# Relay_y_salida_anal_gica.net
KiCad netlist of a schematic drawn in Altium Designer
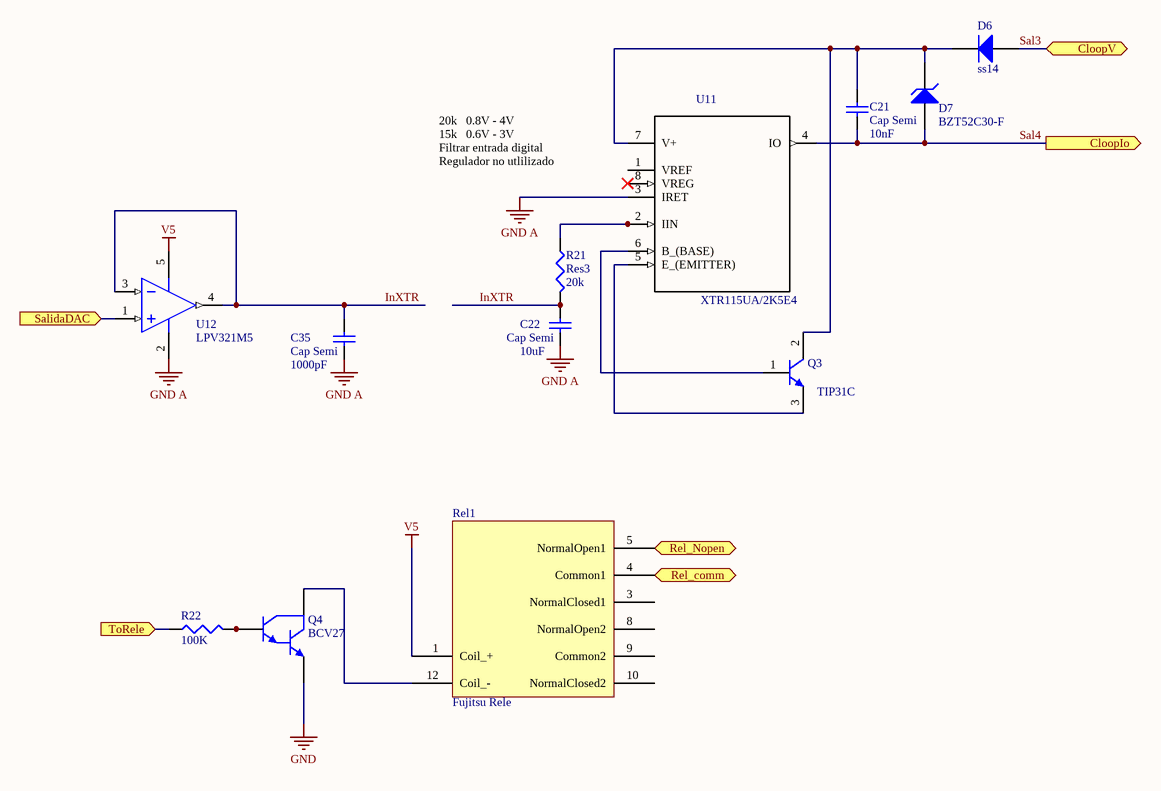
[diagram p0: Relay y salida analógica.SchDoc]

(export (version "E")
  (design (tool "Eeschema 10.0.6"))
  (components
    (comp (ref "C21")
      (value "Cap Semi")
      (footprint "Custom0805")
      (description "Capacitor (Semiconductor SIM Model)")
      (fields (field (name "ALTIUM_VALUE") "10nF") (field (name "PUBLISHER") "Altium Limited"))
      (libsource (lib "Miscellaneous Devices") (part "Cap Semi"))
    )
    (comp (ref "C22")
      (value "Cap Semi")
      (footprint "Custom0805")
      (description "Capacitor (Semiconductor SIM Model)")
      (fields (field (name "ALTIUM_VALUE") "10uF") (field (name "PUBLISHER") "Altium Limited"))
      (libsource (lib "Miscellaneous Devices") (part "Cap Semi"))
    )
    (comp (ref "C35")
      (value "Cap Semi")
      (footprint "Custom0805")
      (description "Capacitor (Semiconductor SIM Model)")
      (fields (field (name "ALTIUM_VALUE") "1000pF") (field (name "PUBLISHER") "Altium Limited"))
      (libsource (lib "Miscellaneous Devices") (part "Cap Semi"))
    )
    (comp (ref "D6")
      (value "ss14")
      (footprint "DO214")
      (description "Default Diode")
      (fields (field (name "PUBLISHER") "Altium Limited"))
      (libsource (lib "Miscellaneous Devices") (part "Diode"))
    )
    (comp (ref "D7")
      (value "BZT52C30-F")
      (footprint "1N4148W")
      (description "Zener Diode SMD")
      (fields (field (name "PUBLISHER") "Altium Limited"))
      (libsource (lib "Miscellaneous Devices") (part "D Zener"))
    )
    (comp (ref "Q3")
      (value "TIP31C")
      (footprint "TO-220AB")
      (description "NPN Bipolar Transistor")
      (fields (field (name "PUBLISHER") "Altium Limited"))
      (libsource (lib "Miscellaneous Devices") (part "NPN"))
    )
    (comp (ref "Q4")
      (value "BCV27")
      (footprint "SOT23_L")
      (description "NPN Darlington Bipolar Transistor")
      (fields (field (name "PUBLISHER") "Altium Limited"))
      (libsource (lib "Miscellaneous Devices") (part "NPN1"))
    )
    (comp (ref "R21")
      (value "Res3")
      (footprint "Custom0805")
      (description "Resistor")
      (fields (field (name "ALTIUM_VALUE") "20k") (field (name "PUBLISHER") "Altium Limited"))
      (libsource (lib "Miscellaneous Devices") (part "Res3"))
    )
    (comp (ref "R22")
      (value "100K")
      (footprint "Custom0805")
      (description "Resistor")
      (fields (field (name "Comment") "Rb") (field (name "PUBLISHER") "Altium Limited"))
      (libsource (lib "Miscellaneous Devices") (part "Res3"))
    )
    (comp (ref "Rel1")
      (value "Fujitsu Rele")
      (footprint "Rele_Fujtsu")
      (description "FBR12ND-05")
      (libsource (lib "therele") (part "Rele_2"))
    )
    (comp (ref "U11")
      (value "XTR115UA/2K5E4")
      (footprint "*SOIC127P600X175-8N")
      (description "Current Loop Transmitter 8-Pin SOIC T/R")
      (fields (field (name "MF") "Texas Instruments"))
      (libsource (lib "XTR115UA_2K5E4") (part "XTR115UA/2K5E4"))
    )
    (comp (ref "U12")
      (value "LPV321M5")
      (footprint "MF05A_N")
      (description "General Purpose, Low Voltage, Low Power, Rail-to-Rail Output Operational Amplifiers, 5-pin SOT-23")
      (fields
        (field (name "MANUFACTURER") "National Semiconductor")
        (field (name "PUBLISHER") "Altium Limited")
      )
      (libsource (lib "NSC Amplifier") (part "LPV321M5"))
    )
  )
  (nets
    (net (code "1") (name "/InXTR") (class "Default")
      (node (ref "C22") (pin "2") (pinfunction "2_2") (pintype "passive"))
      (node (ref "C35") (pin "2") (pinfunction "2_2") (pintype "passive"))
      (node (ref "R21") (pin "2") (pinfunction "2_2") (pintype "passive"))
      (node (ref "U12") (pin "3") (pinfunction "IN-_3") (pintype "input"))
      (node (ref "U12") (pin "4") (pinfunction "OUT_4") (pintype "output"))
    )
    (net (code "2") (name "/Rel_Nopen") (class "Default")
      (node (ref "Rel1") (pin "5") (pinfunction "NormalOpen1_5") (pintype "passive"))
    )
    (net (code "3") (name "/Rel_comm") (class "Default")
      (node (ref "Rel1") (pin "4") (pinfunction "Common1_4") (pintype "passive"))
    )
    (net (code "4") (name "/Sal3") (class "Default")
      (node (ref "D6") (pin "1") (pinfunction "A_1") (pintype "passive"))
    )
    (net (code "5") (name "/Sal4") (class "Default")
      (node (ref "C21") (pin "1") (pinfunction "1_1") (pintype "passive"))
      (node (ref "D7") (pin "1") (pinfunction "A_1") (pintype "passive"))
      (node (ref "U11") (pin "4") (pinfunction "IO_4") (pintype "output"))
    )
    (net (code "6") (name "/SalidaDAC") (class "Default")
      (node (ref "U12") (pin "1") (pinfunction "IN+_1") (pintype "input"))
    )
    (net (code "7") (name "/ToRele") (class "Default")
      (node (ref "R22") (pin "1") (pinfunction "1_1") (pintype "passive"))
    )
    (net (code "8") (name "GND") (class "Default")
      (node (ref "Q4") (pin "2") (pinfunction "E_2") (pintype "passive"))
    )
    (net (code "9") (name "GND A") (class "Default")
      (node (ref "C22") (pin "1") (pinfunction "1_1") (pintype "passive"))
      (node (ref "C35") (pin "1") (pinfunction "1_1") (pintype "passive"))
      (node (ref "U11") (pin "3") (pinfunction "IRET_3") (pintype "passive"))
      (node (ref "U12") (pin "2") (pinfunction "V-_2") (pintype "power_in"))
    )
    (net (code "10") (name "Net-(D6-K)") (class "Default")
      (node (ref "C21") (pin "2") (pinfunction "2_2") (pintype "passive"))
      (node (ref "D6") (pin "2") (pinfunction "K_2") (pintype "passive"))
      (node (ref "D7") (pin "2") (pinfunction "K_2") (pintype "passive"))
      (node (ref "Q3") (pin "2") (pinfunction "C_2") (pintype "passive"))
      (node (ref "U11") (pin "7") (pinfunction "V+_7") (pintype "power_in"))
    )
    (net (code "11") (name "Net-(Q3-B)") (class "Default")
      (node (ref "Q3") (pin "1") (pinfunction "B_1") (pintype "passive"))
      (node (ref "U11") (pin "6") (pinfunction "B_(BASE)_6") (pintype "input"))
    )
    (net (code "12") (name "Net-(Q3-E)") (class "Default")
      (node (ref "Q3") (pin "3") (pinfunction "E_3") (pintype "passive"))
      (node (ref "U11") (pin "5") (pinfunction "E_(EMITTER)_5") (pintype "input"))
    )
    (net (code "13") (name "Net-(Q4-B)") (class "Default")
      (node (ref "Q4") (pin "3") (pinfunction "B_3") (pintype "passive"))
      (node (ref "R22") (pin "2") (pinfunction "2_2") (pintype "passive"))
    )
    (net (code "14") (name "Net-(Q4-C)") (class "Default")
      (node (ref "Q4") (pin "1") (pinfunction "C_1") (pintype "passive"))
      (node (ref "Rel1") (pin "12") (pinfunction "Coil_-_12") (pintype "passive"))
    )
    (net (code "15") (name "Net-(U11-IIN)") (class "Default")
      (node (ref "R21") (pin "1") (pinfunction "1_1") (pintype "passive"))
      (node (ref "U11") (pin "2") (pinfunction "IIN_2") (pintype "input"))
    )
    (net (code "16") (name "V5") (class "Default")
      (node (ref "Rel1") (pin "1") (pinfunction "Coil_+_1") (pintype "passive"))
      (node (ref "U12") (pin "5") (pinfunction "V+_5") (pintype "power_in"))
    )
    (net (code "17") (name "unconnected-(Rel1-Common2-Pad9)") (class "Default")
      (node (ref "Rel1") (pin "9") (pinfunction "Common2_9") (pintype "passive"))
    )
    (net (code "18") (name "unconnected-(Rel1-NormalClosed1-Pad3)") (class "Default")
      (node (ref "Rel1") (pin "3") (pinfunction "NormalClosed1_3") (pintype "passive"))
    )
    (net (code "19") (name "unconnected-(Rel1-NormalClosed2-Pad10)") (class "Default")
      (node (ref "Rel1") (pin "10") (pinfunction "NormalClosed2_10") (pintype "passive"))
    )
    (net (code "20") (name "unconnected-(Rel1-NormalOpen2-Pad8)") (class "Default")
      (node (ref "Rel1") (pin "8") (pinfunction "NormalOpen2_8") (pintype "passive"))
    )
    (net (code "21") (name "unconnected-(U11-VREF-Pad1)") (class "Default")
      (node (ref "U11") (pin "1") (pinfunction "VREF_1") (pintype "passive"))
    )
    (net (code "22") (name "unconnected-(U11-VREG-Pad8)") (class "Default")
      (node (ref "U11") (pin "8") (pinfunction "VREG_8") (pintype "input+no_connect"))
    )
  )
)
